# Micro.net
KiCad netlist of a schematic drawn in Altium Designer
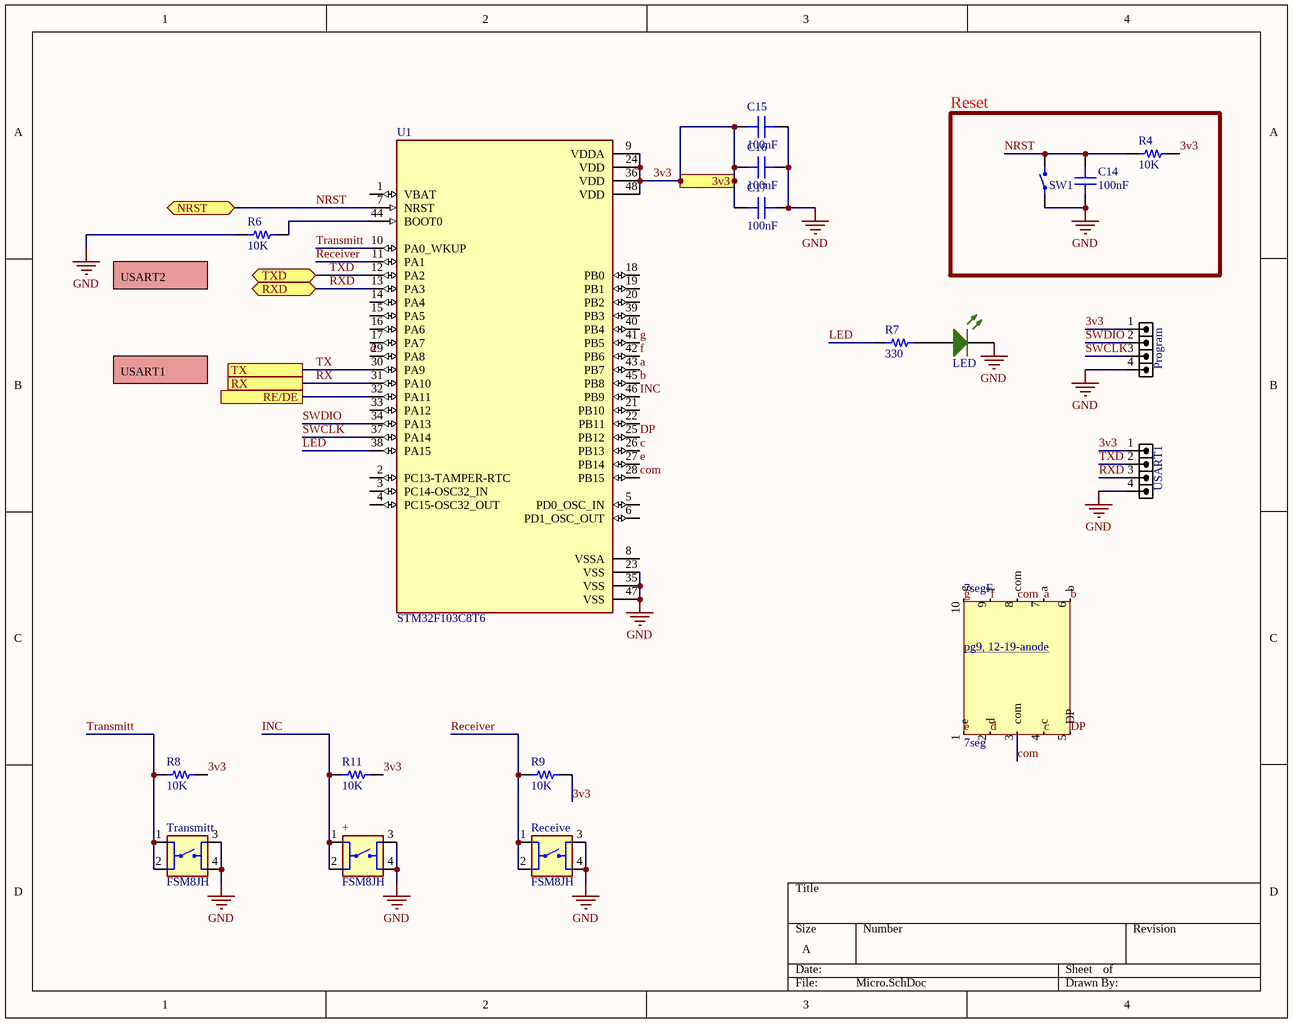
[diagram p0: Micro.SchDoc]

(export (version "E")
  (design (tool "Eeschema 10.0.6"))
  (components
    (comp (ref "+")
      (value "FSM8JH")
      (footprint "SW_FSM8JH")
      (description "Tactile Switch SPST-NO Top Actuated Through Hole")
      (fields (field (name "MF") "TE Connectivity"))
      (libsource (lib "FSM8JH") (part "FSM8JH"))
    )
    (comp (ref "7seg")
      (value "7seg")
      (footprint "PCBComponent_1")
      (description "file:///C:/Users/Tamana/Downloads/7SEG-12-19mm-GREEN-ANOD.pdf")
      (libsource (lib "7seg") (part "7seg"))
    )
    (comp (ref "C14")
      (value "100nF")
      (footprint "CAP 0805_2012")
      (description "SMT Capacitor")
      (libsource (lib "Capacitor") (part "Cap 0805"))
    )
    (comp (ref "C15")
      (value "100nF")
      (footprint "CAP 0805_2012")
      (description "SMT Capacitor")
      (libsource (lib "Capacitor") (part "Cap 0805"))
    )
    (comp (ref "C16")
      (value "100nF")
      (footprint "CAP 0805_2012")
      (description "SMT Capacitor")
      (libsource (lib "Capacitor") (part "Cap 0805"))
    )
    (comp (ref "C17")
      (value "100nF")
      (footprint "CAP 0805_2012")
      (description "SMT Capacitor")
      (libsource (lib "Capacitor") (part "Cap 0805"))
    )
    (comp (ref "LED")
      (value "LED SMD 0805 GREEN")
      (footprint "LED_0805_GREEN")
      (libsource (lib "Led") (part "LED SMD 0805 GREEN"))
    )
    (comp (ref "Program")
      (value "HDR1X4")
      (footprint "HDR_1X4")
      (description "CONN, HEADER, Male, pitch: 2.54mm, 4POS")
      (libsource (lib "Conn Header") (part "HDR_1X4"))
    )
    (comp (ref "R4")
      (value "10K")
      (footprint "RES 0805_2012")
      (description "SMT Resistor")
      (libsource (lib "Resistor") (part "Res 0805"))
    )
    (comp (ref "R6")
      (value "10K")
      (footprint "RES 0805_2012")
      (description "SMT Resistor")
      (libsource (lib "Resistor") (part "Res 0805"))
    )
    (comp (ref "R7")
      (value "330")
      (footprint "RES 0805_2012")
      (description "SMT Resistor")
      (libsource (lib "Resistor") (part "Res 0805"))
    )
    (comp (ref "R8")
      (value "10K")
      (footprint "RES 0805_2012")
      (description "SMT Resistor")
      (libsource (lib "Resistor") (part "Res 0805"))
    )
    (comp (ref "R9")
      (value "10K")
      (footprint "RES 0805_2012")
      (description "SMT Resistor")
      (libsource (lib "Resistor") (part "Res 0805"))
    )
    (comp (ref "R11")
      (value "10K")
      (footprint "RES 0805_2012")
      (description "SMT Resistor")
      (libsource (lib "Resistor") (part "Res 0805"))
    )
    (comp (ref "Receive")
      (value "FSM8JH")
      (footprint "SW_FSM8JH")
      (description "Tactile Switch SPST-NO Top Actuated Through Hole")
      (fields (field (name "MF") "TE Connectivity"))
      (libsource (lib "FSM8JH") (part "FSM8JH"))
    )
    (comp (ref "SW1")
      (value "Tactile 2PIN 6X3.5mm H4.57mm (SMD)")
      (footprint "SWPBS_SPST_6X3X5")
      (description "Tactile Switch SPST-NO Top Actuated Surface Mount")
      (fields (field (name "PARTNUMBER") "FSMSMTR-ND"))
      (libsource (lib "Switch") (part "Tactile 2PIN 6X3.5mm H4.57mm (SMD)"))
    )
    (comp (ref "Transmitt")
      (value "FSM8JH")
      (footprint "SW_FSM8JH")
      (description "Tactile Switch SPST-NO Top Actuated Through Hole")
      (fields (field (name "MF") "TE Connectivity"))
      (libsource (lib "FSM8JH") (part "FSM8JH"))
    )
    (comp (ref "U1")
      (value "STM32F103C8T6")
      (footprint "QFP50P900X900X160-48N")
      (description "ARM® Cortex®-M3 STM32F1 Microcontroller IC 32-Bit 72MHz 64KB (64K x 8) FLASH 48-LQFP (7x7)")
      (fields (field (name "MF") "STMicroelectronics"))
      (libsource (lib "STM32F103C8T6") (part "STM32F103C8T6"))
    )
    (comp (ref "USART1")
      (value "HDR1X4")
      (footprint "HDR_1X4")
      (description "CONN, HEADER, Male, pitch: 2.54mm, 4POS")
      (libsource (lib "Conn Header") (part "HDR_1X4"))
    )
  )
  (nets
    (net (code "1") (name "/3v3") (class "Default")
      (node (ref "C15") (pin "2") (pinfunction "2_2") (pintype "passive"))
      (node (ref "C16") (pin "2") (pinfunction "2_2") (pintype "passive"))
      (node (ref "C17") (pin "2") (pinfunction "2_2") (pintype "passive"))
      (node (ref "Program") (pin "1") (pinfunction "1_1") (pintype "passive"))
      (node (ref "R11") (pin "2") (pinfunction "2_2") (pintype "passive"))
      (node (ref "R4") (pin "2") (pinfunction "2_2") (pintype "passive"))
      (node (ref "R8") (pin "2") (pinfunction "2_2") (pintype "passive"))
      (node (ref "R9") (pin "2") (pinfunction "2_2") (pintype "passive"))
      (node (ref "U1") (pin "24") (pinfunction "VDD_24") (pintype "power_in"))
      (node (ref "U1") (pin "36") (pinfunction "VDD_36") (pintype "power_in"))
      (node (ref "U1") (pin "48") (pinfunction "VDD_48") (pintype "power_in"))
      (node (ref "U1") (pin "9") (pinfunction "VDDA_9") (pintype "power_in"))
      (node (ref "USART1") (pin "1") (pinfunction "1_1") (pintype "passive"))
    )
    (net (code "2") (name "/DP") (class "Default")
      (node (ref "7seg") (pin "5") (pinfunction "DP_5") (pintype "passive"))
      (node (ref "U1") (pin "25") (pinfunction "PB12_25") (pintype "bidirectional"))
    )
    (net (code "3") (name "/INC") (class "Default")
      (node (ref "+") (pin "1") (pinfunction "1_1") (pintype "passive"))
      (node (ref "+") (pin "2") (pinfunction "2_2") (pintype "passive"))
      (node (ref "R11") (pin "1") (pinfunction "1_1") (pintype "passive"))
      (node (ref "U1") (pin "46") (pinfunction "PB9_46") (pintype "bidirectional"))
    )
    (net (code "4") (name "/LED") (class "Default")
      (node (ref "R7") (pin "1") (pinfunction "1_1") (pintype "passive"))
      (node (ref "U1") (pin "38") (pinfunction "PA15_38") (pintype "bidirectional"))
    )
    (net (code "5") (name "/NRST") (class "Default")
      (node (ref "C14") (pin "2") (pinfunction "2_2") (pintype "passive"))
      (node (ref "R4") (pin "1") (pinfunction "1_1") (pintype "passive"))
      (node (ref "SW1") (pin "2") (pinfunction "2_2") (pintype "passive"))
      (node (ref "U1") (pin "7") (pinfunction "NRST_7") (pintype "input"))
    )
    (net (code "6") (name "/RE{slash}DE") (class "Default")
      (node (ref "U1") (pin "32") (pinfunction "PA11_32") (pintype "bidirectional"))
    )
    (net (code "7") (name "/RX") (class "Default")
      (node (ref "U1") (pin "31") (pinfunction "PA10_31") (pintype "bidirectional"))
    )
    (net (code "8") (name "/RXD") (class "Default")
      (node (ref "U1") (pin "13") (pinfunction "PA3_13") (pintype "bidirectional"))
      (node (ref "USART1") (pin "3") (pinfunction "3_3") (pintype "passive"))
    )
    (net (code "9") (name "/Receiver") (class "Default")
      (node (ref "R9") (pin "1") (pinfunction "1_1") (pintype "passive"))
      (node (ref "Receive") (pin "1") (pinfunction "1_1") (pintype "passive"))
      (node (ref "Receive") (pin "2") (pinfunction "2_2") (pintype "passive"))
      (node (ref "U1") (pin "11") (pinfunction "PA1_11") (pintype "bidirectional"))
    )
    (net (code "10") (name "/SWCLK") (class "Default")
      (node (ref "Program") (pin "3") (pinfunction "3_3") (pintype "passive"))
      (node (ref "U1") (pin "37") (pinfunction "PA14_37") (pintype "bidirectional"))
    )
    (net (code "11") (name "/SWDIO") (class "Default")
      (node (ref "Program") (pin "2") (pinfunction "2_2") (pintype "passive"))
      (node (ref "U1") (pin "34") (pinfunction "PA13_34") (pintype "bidirectional"))
    )
    (net (code "12") (name "/TX") (class "Default")
      (node (ref "U1") (pin "30") (pinfunction "PA9_30") (pintype "bidirectional"))
    )
    (net (code "13") (name "/TXD") (class "Default")
      (node (ref "U1") (pin "12") (pinfunction "PA2_12") (pintype "bidirectional"))
      (node (ref "USART1") (pin "2") (pinfunction "2_2") (pintype "passive"))
    )
    (net (code "14") (name "/Transmitt") (class "Default")
      (node (ref "R8") (pin "1") (pinfunction "1_1") (pintype "passive"))
      (node (ref "Transmitt") (pin "1") (pinfunction "1_1") (pintype "passive"))
      (node (ref "Transmitt") (pin "2") (pinfunction "2_2") (pintype "passive"))
      (node (ref "U1") (pin "10") (pinfunction "PA0_WKUP_10") (pintype "bidirectional"))
    )
    (net (code "15") (name "/a") (class "Default")
      (node (ref "7seg") (pin "7") (pinfunction "a_7") (pintype "passive"))
      (node (ref "U1") (pin "43") (pinfunction "PB7_43") (pintype "bidirectional"))
    )
    (net (code "16") (name "/b") (class "Default")
      (node (ref "7seg") (pin "6") (pinfunction "b_6") (pintype "passive"))
      (node (ref "U1") (pin "45") (pinfunction "PB8_45") (pintype "bidirectional"))
    )
    (net (code "17") (name "/c") (class "Default")
      (node (ref "7seg") (pin "4") (pinfunction "c_4") (pintype "passive"))
      (node (ref "U1") (pin "26") (pinfunction "PB13_26") (pintype "bidirectional"))
    )
    (net (code "18") (name "/com") (class "Default")
      (node (ref "7seg") (pin "3") (pinfunction "com_3") (pintype "passive"))
      (node (ref "7seg") (pin "8") (pinfunction "com_8") (pintype "passive"))
      (node (ref "U1") (pin "28") (pinfunction "PB15_28") (pintype "bidirectional"))
    )
    (net (code "19") (name "/d") (class "Default")
      (node (ref "7seg") (pin "2") (pinfunction "d_2") (pintype "passive"))
      (node (ref "U1") (pin "29") (pinfunction "PA8_29") (pintype "bidirectional"))
    )
    (net (code "20") (name "/e") (class "Default")
      (node (ref "7seg") (pin "1") (pinfunction "e_1") (pintype "passive"))
      (node (ref "U1") (pin "27") (pinfunction "PB14_27") (pintype "bidirectional"))
    )
    (net (code "21") (name "/f") (class "Default")
      (node (ref "7seg") (pin "9") (pinfunction "f_9") (pintype "passive"))
      (node (ref "U1") (pin "42") (pinfunction "PB6_42") (pintype "bidirectional"))
    )
    (net (code "22") (name "/g") (class "Default")
      (node (ref "7seg") (pin "10") (pinfunction "g_10") (pintype "passive"))
      (node (ref "U1") (pin "41") (pinfunction "PB5_41") (pintype "bidirectional"))
    )
    (net (code "23") (name "GND") (class "Default")
      (node (ref "+") (pin "3") (pinfunction "3_3") (pintype "passive"))
      (node (ref "+") (pin "4") (pinfunction "4_4") (pintype "passive"))
      (node (ref "C14") (pin "1") (pinfunction "1_1") (pintype "passive"))
      (node (ref "C15") (pin "1") (pinfunction "1_1") (pintype "passive"))
      (node (ref "C16") (pin "1") (pinfunction "1_1") (pintype "passive"))
      (node (ref "C17") (pin "1") (pinfunction "1_1") (pintype "passive"))
      (node (ref "LED") (pin "2") (pinfunction "K_2") (pintype "passive"))
      (node (ref "Program") (pin "4") (pinfunction "4_4") (pintype "passive"))
      (node (ref "R6") (pin "1") (pinfunction "1_1") (pintype "passive"))
      (node (ref "Receive") (pin "3") (pinfunction "3_3") (pintype "passive"))
      (node (ref "Receive") (pin "4") (pinfunction "4_4") (pintype "passive"))
      (node (ref "SW1") (pin "1") (pinfunction "1_1") (pintype "passive"))
      (node (ref "Transmitt") (pin "3") (pinfunction "3_3") (pintype "passive"))
      (node (ref "Transmitt") (pin "4") (pinfunction "4_4") (pintype "passive"))
      (node (ref "U1") (pin "23") (pinfunction "VSS_23") (pintype "power_in"))
      (node (ref "U1") (pin "35") (pinfunction "VSS_35") (pintype "power_in"))
      (node (ref "U1") (pin "47") (pinfunction "VSS_47") (pintype "power_in"))
      (node (ref "USART1") (pin "4") (pinfunction "4_4") (pintype "passive"))
    )
    (net (code "24") (name "Net-(LED-A)") (class "Default")
      (node (ref "LED") (pin "1") (pinfunction "A_1") (pintype "passive"))
      (node (ref "R7") (pin "2") (pinfunction "2_2") (pintype "passive"))
    )
    (net (code "25") (name "Net-(U1-BOOT0)") (class "Default")
      (node (ref "R6") (pin "2") (pinfunction "2_2") (pintype "passive"))
      (node (ref "U1") (pin "44") (pinfunction "BOOT0_44") (pintype "input"))
    )
    (net (code "26") (name "unconnected-(U1-PA4-Pad14)") (class "Default")
      (node (ref "U1") (pin "14") (pinfunction "PA4_14") (pintype "bidirectional"))
    )
    (net (code "27") (name "unconnected-(U1-PA5-Pad15)") (class "Default")
      (node (ref "U1") (pin "15") (pinfunction "PA5_15") (pintype "bidirectional"))
    )
    (net (code "28") (name "unconnected-(U1-PA6-Pad16)") (class "Default")
      (node (ref "U1") (pin "16") (pinfunction "PA6_16") (pintype "bidirectional"))
    )
    (net (code "29") (name "unconnected-(U1-PA7-Pad17)") (class "Default")
      (node (ref "U1") (pin "17") (pinfunction "PA7_17") (pintype "bidirectional"))
    )
    (net (code "30") (name "unconnected-(U1-PA12-Pad33)") (class "Default")
      (node (ref "U1") (pin "33") (pinfunction "PA12_33") (pintype "bidirectional"))
    )
    (net (code "31") (name "unconnected-(U1-PB0-Pad18)") (class "Default")
      (node (ref "U1") (pin "18") (pinfunction "PB0_18") (pintype "bidirectional"))
    )
    (net (code "32") (name "unconnected-(U1-PB1-Pad19)") (class "Default")
      (node (ref "U1") (pin "19") (pinfunction "PB1_19") (pintype "bidirectional"))
    )
    (net (code "33") (name "unconnected-(U1-PB2-Pad20)") (class "Default")
      (node (ref "U1") (pin "20") (pinfunction "PB2_20") (pintype "bidirectional"))
    )
    (net (code "34") (name "unconnected-(U1-PB3-Pad39)") (class "Default")
      (node (ref "U1") (pin "39") (pinfunction "PB3_39") (pintype "bidirectional"))
    )
    (net (code "35") (name "unconnected-(U1-PB4-Pad40)") (class "Default")
      (node (ref "U1") (pin "40") (pinfunction "PB4_40") (pintype "bidirectional"))
    )
    (net (code "36") (name "unconnected-(U1-PB10-Pad21)") (class "Default")
      (node (ref "U1") (pin "21") (pinfunction "PB10_21") (pintype "bidirectional"))
    )
    (net (code "37") (name "unconnected-(U1-PB11-Pad22)") (class "Default")
      (node (ref "U1") (pin "22") (pinfunction "PB11_22") (pintype "bidirectional"))
    )
    (net (code "38") (name "unconnected-(U1-PC13-TAMPER-RTC-Pad2)") (class "Default")
      (node (ref "U1") (pin "2") (pinfunction "PC13-TAMPER-RTC_2") (pintype "bidirectional"))
    )
    (net (code "39") (name "unconnected-(U1-PC14-OSC32_IN-Pad3)") (class "Default")
      (node (ref "U1") (pin "3") (pinfunction "PC14-OSC32_IN_3") (pintype "bidirectional"))
    )
    (net (code "40") (name "unconnected-(U1-PC15-OSC32_OUT-Pad4)") (class "Default")
      (node (ref "U1") (pin "4") (pinfunction "PC15-OSC32_OUT_4") (pintype "bidirectional"))
    )
    (net (code "41") (name "unconnected-(U1-PD0_OSC_IN-Pad5)") (class "Default")
      (node (ref "U1") (pin "5") (pinfunction "PD0_OSC_IN_5") (pintype "bidirectional"))
    )
    (net (code "42") (name "unconnected-(U1-PD1_OSC_OUT-Pad6)") (class "Default")
      (node (ref "U1") (pin "6") (pinfunction "PD1_OSC_OUT_6") (pintype "bidirectional"))
    )
    (net (code "43") (name "unconnected-(U1-VBAT-Pad1)") (class "Default")
      (node (ref "U1") (pin "1") (pinfunction "VBAT_1") (pintype "bidirectional"))
    )
    (net (code "44") (name "unconnected-(U1-VSSA-Pad8)") (class "Default")
      (node (ref "U1") (pin "8") (pinfunction "VSSA_8") (pintype "power_in"))
    )
  )
)
